# 01_InputStage_v1.net
KiCad netlist of a schematic drawn in EAGLE
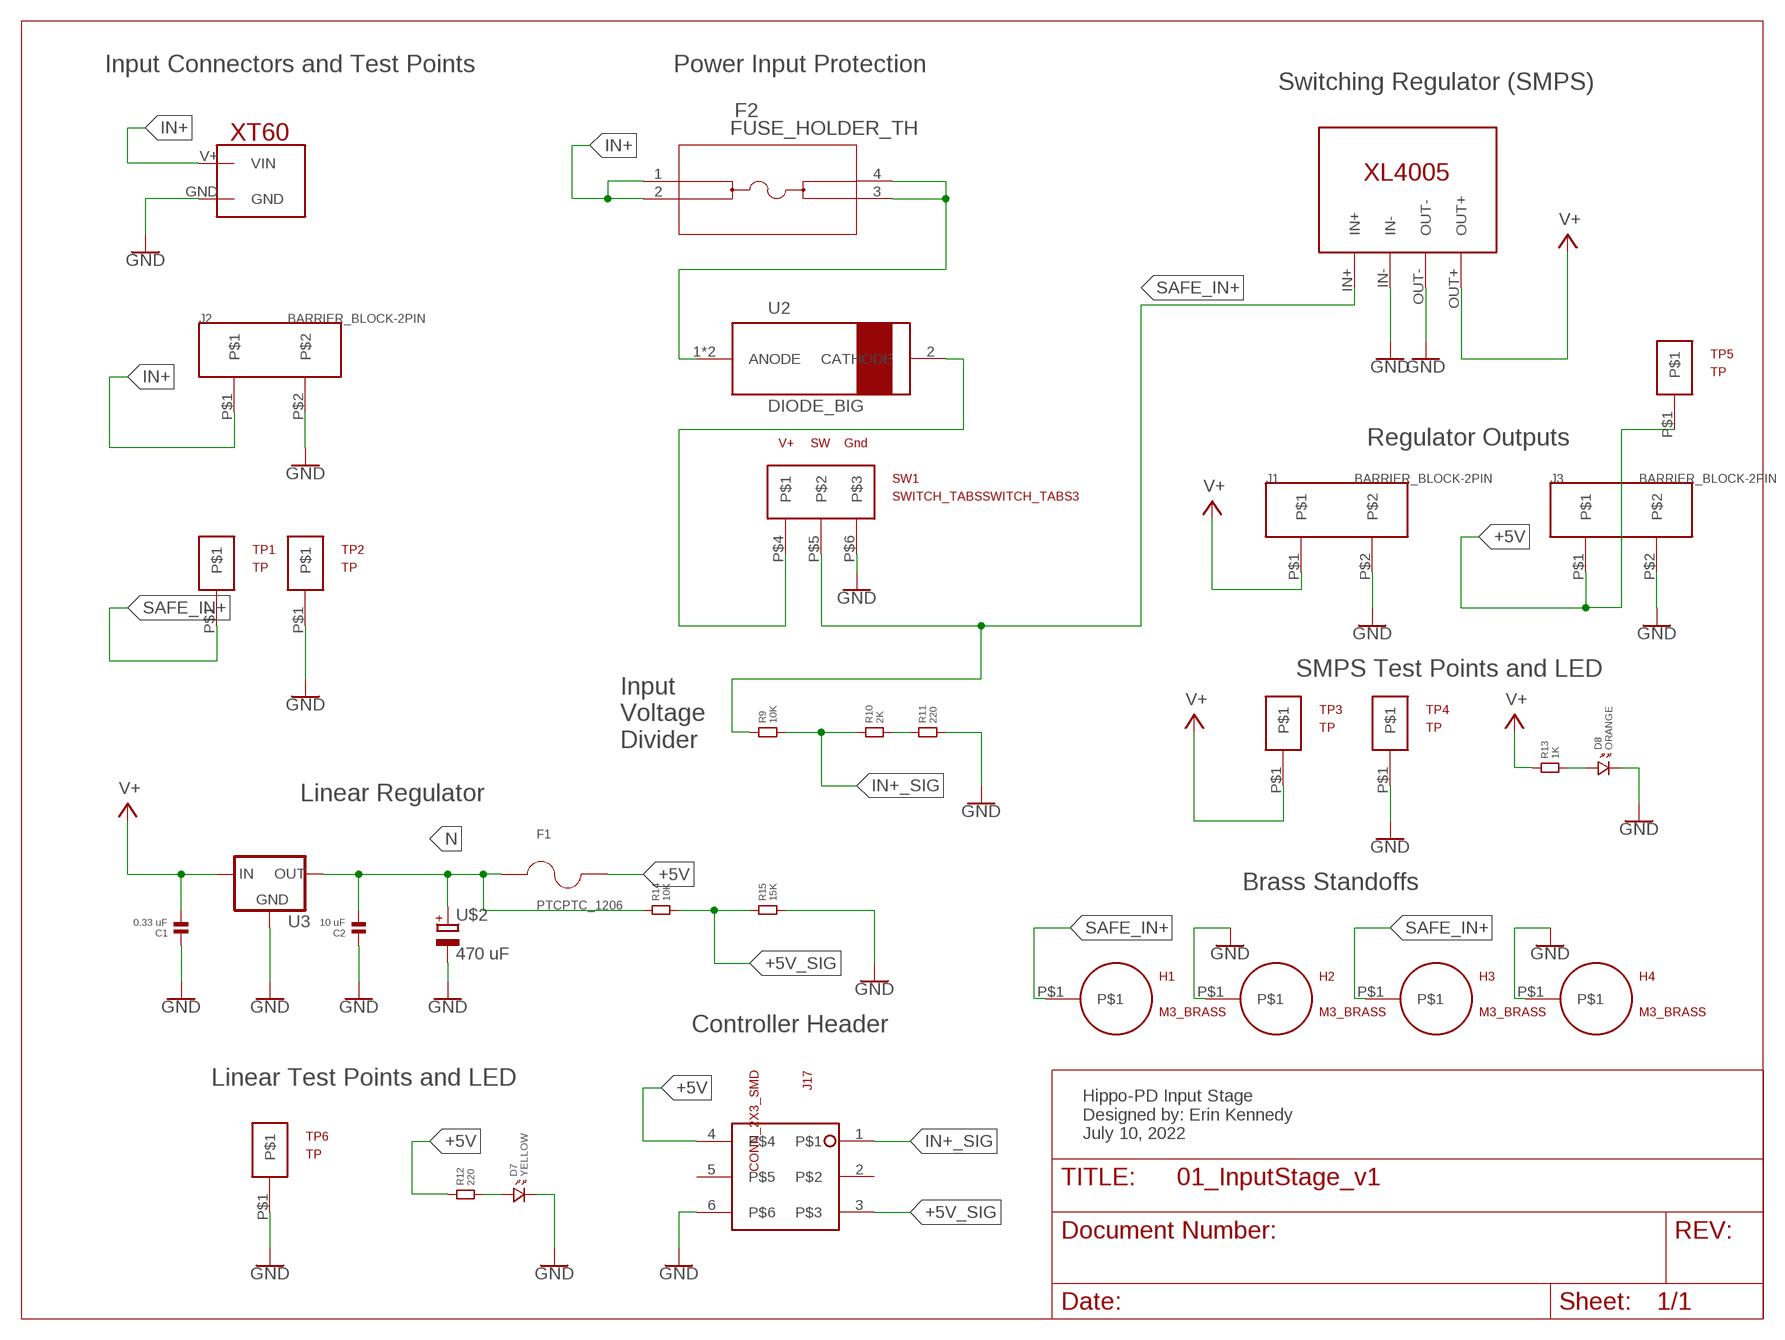
[diagram p0: schematic, sheet 1]

(export (version "E")
  (design (tool "Eeschema 10.0.6"))
  (components
    (comp (ref "C1")
      (value "0.33 uF")
      (footprint "eagle-import:1206")
      (libsource (lib "eagle-import") (part "CAPACITOR.1206"))
    )
    (comp (ref "C2")
      (value "10 uF")
      (footprint "eagle-import:1206")
      (libsource (lib "eagle-import") (part "CAPACITOR.1206"))
    )
    (comp (ref "D7")
      (value "YELLOW")
      (footprint "eagle-import:1206.LED")
      (libsource (lib "eagle-import") (part "LED.1206"))
    )
    (comp (ref "D8")
      (value "ORANGE")
      (footprint "eagle-import:1206.LED")
      (libsource (lib "eagle-import") (part "LED.1206"))
    )
    (comp (ref "F1")
      (value "PTCPTC_1206")
      (footprint "eagle-import:1206")
      (libsource (lib "eagle-import") (part "PTCPTC_1206"))
    )
    (comp (ref "F2")
      (value "FUSE_HOLDER_TH")
      (footprint "eagle-import:FUSE_HOLDER_TH")
      (fields
        (field (name "MANUFACTURER_PART_NUMBER") "3557-10")
        (field (name "COPYRIGHT") "Copyright (C) 2022 Ultra Librarian. All rights reserved.")
      )
      (libsource (lib "eagle-import") (part "FUSE_HOLDER_TH"))
    )
    (comp (ref "H1")
      (value "M3_BRASS")
      (footprint "eagle-import:M3_BRASS")
      (libsource (lib "eagle-import") (part "M3_BRASS"))
    )
    (comp (ref "H2")
      (value "M3_BRASS")
      (footprint "eagle-import:M3_BRASS")
      (libsource (lib "eagle-import") (part "M3_BRASS"))
    )
    (comp (ref "H3")
      (value "M3_BRASS")
      (footprint "eagle-import:M3_BRASS")
      (libsource (lib "eagle-import") (part "M3_BRASS"))
    )
    (comp (ref "H4")
      (value "M3_BRASS")
      (footprint "eagle-import:M3_BRASS")
      (libsource (lib "eagle-import") (part "M3_BRASS"))
    )
    (comp (ref "J1")
      (value "BARRIER_BLOCK-2PIN")
      (footprint "eagle-import:BARRIERBLOCK-2PIN")
      (libsource (lib "eagle-import") (part "BARRIER_BLOCK-2PIN"))
    )
    (comp (ref "J2")
      (value "BARRIER_BLOCK-2PIN")
      (footprint "eagle-import:BARRIERBLOCK-2PIN")
      (libsource (lib "eagle-import") (part "BARRIER_BLOCK-2PIN"))
    )
    (comp (ref "J3")
      (value "BARRIER_BLOCK-2PIN")
      (footprint "eagle-import:BARRIERBLOCK-2PIN")
      (libsource (lib "eagle-import") (part "BARRIER_BLOCK-2PIN"))
    )
    (comp (ref "J17")
      (value "CONN_2X3_SMD")
      (footprint "eagle-import:2X3_SMD_CONNECTOR")
      (libsource (lib "eagle-import") (part "CONN_2X3_SMD"))
    )
    (comp (ref "R9")
      (value "10K")
      (footprint "eagle-import:1206")
      (libsource (lib "eagle-import") (part "RESISTOR.1206"))
    )
    (comp (ref "R10")
      (value "2K")
      (footprint "eagle-import:1206")
      (libsource (lib "eagle-import") (part "RESISTOR.1206"))
    )
    (comp (ref "R11")
      (value "220")
      (footprint "eagle-import:1206")
      (libsource (lib "eagle-import") (part "RESISTOR.1206"))
    )
    (comp (ref "R12")
      (value "220")
      (footprint "eagle-import:1206")
      (libsource (lib "eagle-import") (part "RESISTOR.1206"))
    )
    (comp (ref "R13")
      (value "1K")
      (footprint "eagle-import:1206")
      (libsource (lib "eagle-import") (part "RESISTOR.1206"))
    )
    (comp (ref "R14")
      (value "10K")
      (footprint "eagle-import:1206")
      (libsource (lib "eagle-import") (part "RESISTOR.1206"))
    )
    (comp (ref "R15")
      (value "15K")
      (footprint "eagle-import:1206")
      (libsource (lib "eagle-import") (part "RESISTOR.1206"))
    )
    (comp (ref "SW1")
      (value "SWITCH_TABSSWITCH_TABS3")
      (footprint "eagle-import:SWITCH_TABS3")
      (libsource (lib "eagle-import") (part "SWITCH_TABSSWITCH_TABS3"))
    )
    (comp (ref "TP1") (value "TP") (footprint "eagle-import:TP") (libsource (lib "eagle-import") (part "TP")))
    (comp (ref "TP2") (value "TP") (footprint "eagle-import:TP") (libsource (lib "eagle-import") (part "TP")))
    (comp (ref "TP3") (value "TP") (footprint "eagle-import:TP") (libsource (lib "eagle-import") (part "TP")))
    (comp (ref "TP4") (value "TP") (footprint "eagle-import:TP") (libsource (lib "eagle-import") (part "TP")))
    (comp (ref "TP5") (value "TP") (footprint "eagle-import:TP") (libsource (lib "eagle-import") (part "TP")))
    (comp (ref "TP6") (value "TP") (footprint "eagle-import:TP") (libsource (lib "eagle-import") (part "TP")))
    (comp (ref "U$2")
      (value "470 uF")
      (footprint "eagle-import:ELECTROLYTIC_CAP")
      (fields (field (name "MF") "Wurth Electronics") (field (name "MP") "865080545012"))
      (libsource (lib "eagle-import") (part "ELECTROLYTIC_CAP"))
    )
    (comp (ref "U$5")
      (value "XT60")
      (footprint "eagle-import:XT60")
      (libsource (lib "eagle-import") (part "XT60"))
    )
    (comp (ref "U1")
      (value "XL4005-DEV")
      (footprint "eagle-import:XL4005-DEV")
      (libsource (lib "eagle-import") (part "XL4005-DEV"))
    )
    (comp (ref "U2")
      (value "DIODE_BIG")
      (footprint "eagle-import:DIODE_BIG")
      (fields (field (name "MF") "Taiwan Semiconductor Corporation") (field (name "MP") "TS2940CM50 RNG"))
      (libsource (lib "eagle-import") (part "DIODE_BIG"))
    )
    (comp (ref "U3")
      (value "V_REG_78XXSINK")
      (footprint "eagle-import:TO220-IGO")
      (libsource (lib "eagle-import") (part "V_REG_78XXSINK"))
    )
  )
  (nets
    (net (code "1") (name "+5V") (class "Default")
      (node (ref "F1") (pin "2") (pinfunction "2_2") (pintype "passive"))
      (node (ref "J17") (pin "4") (pinfunction "P$4_4") (pintype "bidirectional"))
      (node (ref "J3") (pin "P$1") (pinfunction "P$1_P$1") (pintype "bidirectional"))
      (node (ref "R12") (pin "1") (pinfunction "1_1") (pintype "bidirectional"))
      (node (ref "TP5") (pin "P$1") (pinfunction "P$1_P$1") (pintype "bidirectional"))
    )
    (net (code "2") (name "+5V_SIG") (class "Default")
      (node (ref "J17") (pin "3") (pinfunction "P$3_3") (pintype "bidirectional"))
      (node (ref "R14") (pin "2") (pinfunction "2_2") (pintype "bidirectional"))
      (node (ref "R15") (pin "1") (pinfunction "1_1") (pintype "bidirectional"))
    )
    (net (code "3") (name "GND") (class "Default")
      (node (ref "C1") (pin "1") (pinfunction "1_1") (pintype "bidirectional"))
      (node (ref "C2") (pin "1") (pinfunction "1_1") (pintype "bidirectional"))
      (node (ref "D7") (pin "P$2") (pinfunction "2_P$2") (pintype "bidirectional"))
      (node (ref "D8") (pin "P$2") (pinfunction "2_P$2") (pintype "bidirectional"))
      (node (ref "H2") (pin "P$1") (pinfunction "P$1_P$1") (pintype "bidirectional"))
      (node (ref "H4") (pin "P$1") (pinfunction "P$1_P$1") (pintype "bidirectional"))
      (node (ref "J1") (pin "P$2") (pinfunction "P$2_P$2") (pintype "bidirectional"))
      (node (ref "J17") (pin "6") (pinfunction "P$6_6") (pintype "bidirectional"))
      (node (ref "J2") (pin "P$2") (pinfunction "P$2_P$2") (pintype "bidirectional"))
      (node (ref "J3") (pin "P$2") (pinfunction "P$2_P$2") (pintype "bidirectional"))
      (node (ref "R11") (pin "2") (pinfunction "2_2") (pintype "bidirectional"))
      (node (ref "R15") (pin "2") (pinfunction "2_2") (pintype "bidirectional"))
      (node (ref "SW1") (pin "P$6") (pinfunction "P$3_P$6") (pintype "bidirectional"))
      (node (ref "TP2") (pin "P$1") (pinfunction "P$1_P$1") (pintype "bidirectional"))
      (node (ref "TP4") (pin "P$1") (pinfunction "P$1_P$1") (pintype "bidirectional"))
      (node (ref "TP6") (pin "P$1") (pinfunction "P$1_P$1") (pintype "bidirectional"))
      (node (ref "U$2") (pin "-") (pinfunction "-_-") (pintype "passive"))
      (node (ref "U$5") (pin "GND") (pinfunction "GND_GND") (pintype "bidirectional"))
      (node (ref "U1") (pin "IN-") (pinfunction "IN-_IN-") (pintype "bidirectional"))
      (node (ref "U1") (pin "OUT-") (pinfunction "OUT-_OUT-") (pintype "bidirectional"))
      (node (ref "U3") (pin "GND") (pinfunction "GND_GND") (pintype "input"))
    )
    (net (code "4") (name "IN+") (class "Default")
      (node (ref "F2") (pin "1") (pinfunction "1_1") (pintype "passive"))
      (node (ref "F2") (pin "2") (pinfunction "2_2") (pintype "passive"))
      (node (ref "J2") (pin "P$1") (pinfunction "P$1_P$1") (pintype "bidirectional"))
      (node (ref "U$5") (pin "V+") (pinfunction "VIN_V+") (pintype "bidirectional"))
    )
    (net (code "5") (name "IN+_SIG") (class "Default")
      (node (ref "J17") (pin "1") (pinfunction "P$1_1") (pintype "bidirectional"))
      (node (ref "R10") (pin "1") (pinfunction "1_1") (pintype "bidirectional"))
      (node (ref "R9") (pin "2") (pinfunction "2_2") (pintype "bidirectional"))
    )
    (net (code "6") (name "N") (class "Default")
      (node (ref "C2") (pin "2") (pinfunction "2_2") (pintype "bidirectional"))
      (node (ref "F1") (pin "1") (pinfunction "1_1") (pintype "passive"))
      (node (ref "R14") (pin "1") (pinfunction "1_1") (pintype "bidirectional"))
      (node (ref "U$2") (pin "+") (pinfunction "+_+") (pintype "passive"))
      (node (ref "U3") (pin "OUT") (pinfunction "OUT_OUT") (pintype "passive"))
    )
    (net (code "7") (name "Net-(D7-1)") (class "Default")
      (node (ref "D7") (pin "P$1") (pinfunction "1_P$1") (pintype "bidirectional"))
      (node (ref "R12") (pin "2") (pinfunction "2_2") (pintype "bidirectional"))
    )
    (net (code "8") (name "Net-(D8-1)") (class "Default")
      (node (ref "D8") (pin "P$1") (pinfunction "1_P$1") (pintype "bidirectional"))
      (node (ref "R13") (pin "2") (pinfunction "2_2") (pintype "bidirectional"))
    )
    (net (code "9") (name "Net-(F2-Pad3)") (class "Default")
      (node (ref "F2") (pin "3") (pinfunction "3_3") (pintype "passive"))
      (node (ref "F2") (pin "4") (pinfunction "4_4") (pintype "passive"))
      (node (ref "U2") (pin "1") (pinfunction "ANODE_1") (pintype "input"))
      (node (ref "U2") (pin "3") (pinfunction "ANODE_3") (pintype "input"))
    )
    (net (code "10") (name "Net-(R10-Pad2)") (class "Default")
      (node (ref "R10") (pin "2") (pinfunction "2_2") (pintype "bidirectional"))
      (node (ref "R11") (pin "1") (pinfunction "1_1") (pintype "bidirectional"))
    )
    (net (code "11") (name "Net-(SW1-P$1)") (class "Default")
      (node (ref "SW1") (pin "P$4") (pinfunction "P$1_P$4") (pintype "bidirectional"))
      (node (ref "U2") (pin "2") (pinfunction "CATHODE_2") (pintype "output"))
    )
    (net (code "12") (name "SAFE_IN+") (class "Default")
      (node (ref "H1") (pin "P$1") (pinfunction "P$1_P$1") (pintype "bidirectional"))
      (node (ref "H3") (pin "P$1") (pinfunction "P$1_P$1") (pintype "bidirectional"))
      (node (ref "R9") (pin "1") (pinfunction "1_1") (pintype "bidirectional"))
      (node (ref "SW1") (pin "P$5") (pinfunction "P$2_P$5") (pintype "bidirectional"))
      (node (ref "TP1") (pin "P$1") (pinfunction "P$1_P$1") (pintype "bidirectional"))
      (node (ref "U1") (pin "IN+") (pinfunction "IN+_IN+") (pintype "bidirectional"))
    )
    (net (code "13") (name "V+") (class "Default")
      (node (ref "C1") (pin "2") (pinfunction "2_2") (pintype "bidirectional"))
      (node (ref "J1") (pin "P$1") (pinfunction "P$1_P$1") (pintype "bidirectional"))
      (node (ref "R13") (pin "1") (pinfunction "1_1") (pintype "bidirectional"))
      (node (ref "TP3") (pin "P$1") (pinfunction "P$1_P$1") (pintype "bidirectional"))
      (node (ref "U1") (pin "OUT+") (pinfunction "OUT+_OUT+") (pintype "bidirectional"))
      (node (ref "U3") (pin "IN") (pinfunction "IN_IN") (pintype "input"))
    )
    (net (code "14") (name "unconnected-(J17-P$2-Pad2)") (class "Default")
      (node (ref "J17") (pin "2") (pinfunction "P$2_2") (pintype "bidirectional"))
    )
    (net (code "15") (name "unconnected-(J17-P$5-Pad5)") (class "Default")
      (node (ref "J17") (pin "5") (pinfunction "P$5_5") (pintype "bidirectional"))
    )
  )
)
